# Schematic.net
KiCad netlist of a schematic drawn in Altium Designer
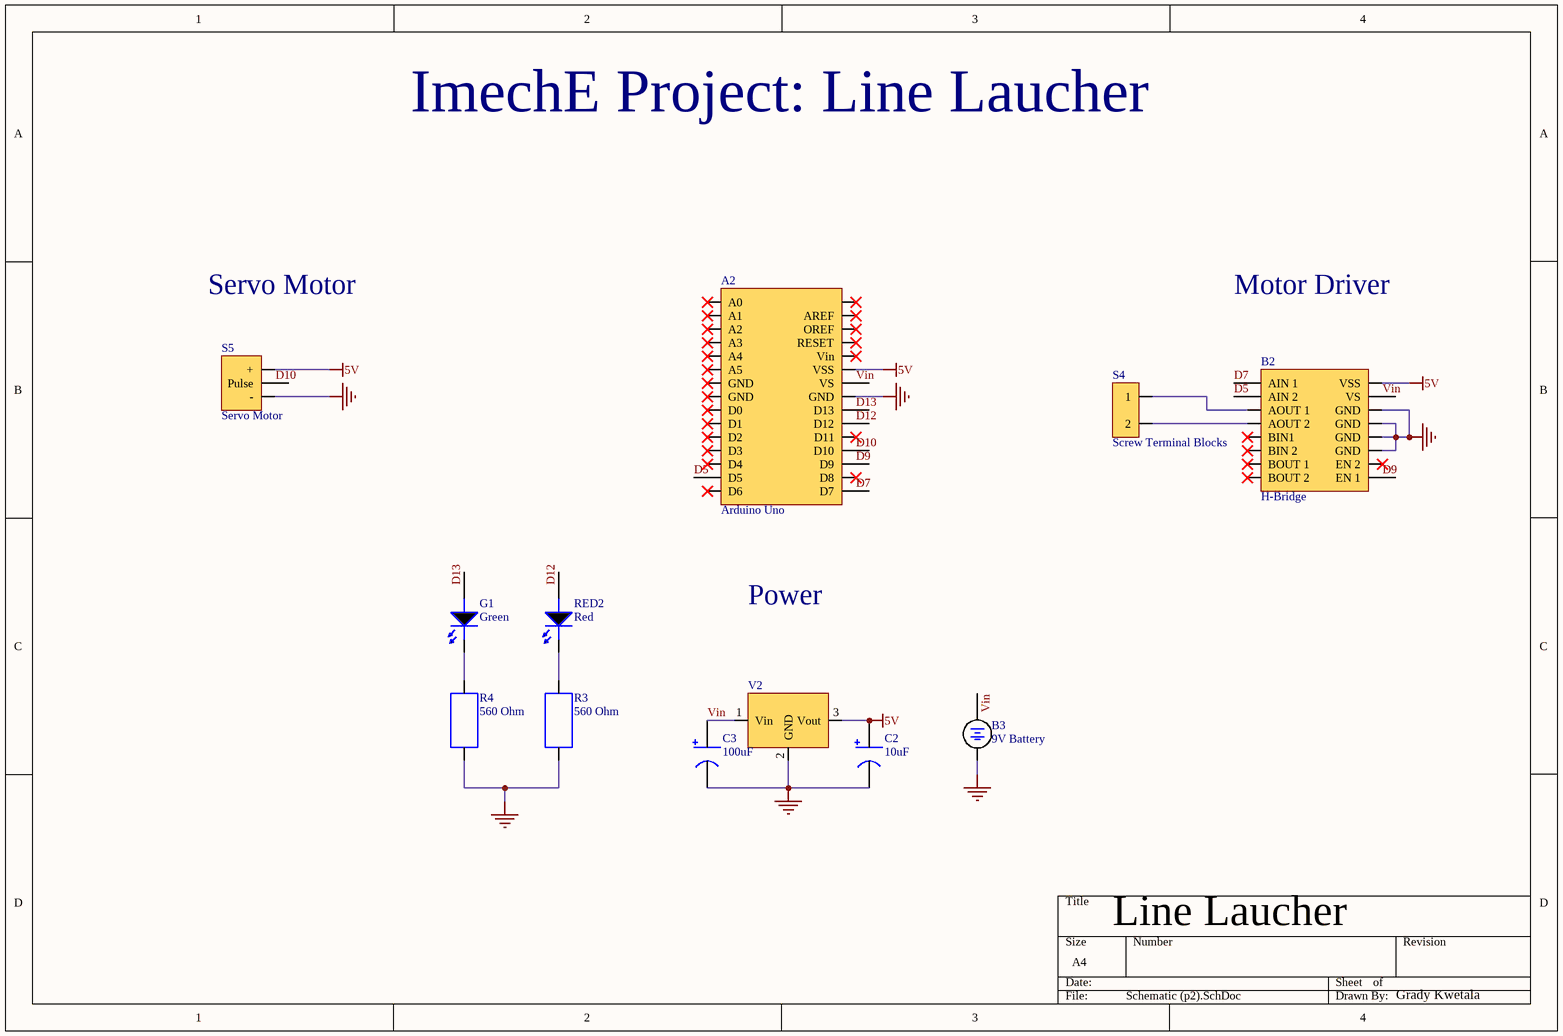
[diagram p0: Schematic (p2).SchDoc]

(export (version "E")
  (design (tool "Eeschema 10.0.6"))
  (components
    (comp (ref "A2")
      (value "Arduino Uno")
      (footprint "Arduino Uno")
      (description "16-bit Microcontrollers - MCU Mixed Signal MCU")
      (fields
        (field (name "MANUFACTURER") "Texas Instruments")
        (field (name "MANUFACTURER PART NUMBER") "MSP430FR5739IDA")
      )
      (libsource (lib "Schematic Library") (part "MSP430FR5739IDA"))
    )
    (comp (ref "B2")
      (value "H-Bridge")
      (footprint "H-Bridge")
      (description "TEXAS INSTRUMENTS - SN754410NE - IC, PERIPHERAL DRIVER, HALF-H, 1A, DIP16")
      (fields
        (field (name "MANUFACTURER") "Texas Instruments")
        (field (name "MANUFACTURER PART NUMBER") "SN754410NE")
      )
      (libsource (lib "Schematic Library") (part "SN754410NE"))
    )
    (comp (ref "B3")
      (value "9V Battery")
      (footprint "9V Battery")
      (description "BATTERY ALKALINE 9V")
      (fields
        (field (name "MANUFACTURER") "Panasonic")
        (field (name "MANUFACTURER PART NUMBER") "6LF22XWA/B")
      )
      (libsource (lib "Schematic Library") (part "6LF22XWA/B"))
    )
    (comp (ref "C2")
      (value "10uF")
      (footprint "10uF")
      (description "Cap Aluminum Lytic 10uF 400V 20% (10 X 16mm) Radial 5mm 150mA 8000h 105C Ammo Pack")
      (fields
        (field (name "MANUFACTURER") "Nichicon")
        (field (name "MANUFACTURER PART NUMBER") "UCY2G100MPD1TD")
      )
      (libsource (lib "Schematic Library") (part "UCY2G100MPD1TD"))
    )
    (comp (ref "C3") (value "100uF") (footprint "100uF") (libsource (lib "Schematic Library") (part "100uF")))
    (comp (ref "G1")
      (value "Green")
      (footprint "Green")
      (description "LED Uni-Color Green 574nm 2-Pin Chip LED T/R")
      (fields
        (field (name "MANUFACTURER") "Vishay Lite-On")
        (field (name "MANUFACTURER PART NUMBER") "LTST-C191KGKT")
      )
      (libsource (lib "Schematic Library") (part "LTST-C191KGKT"))
    )
    (comp (ref "R3")
      (value "560 Ohm")
      (footprint "560")
      (description "Res Thick Film 0805 560 Ohm 1% 0.125W(1/8W) ±100ppm/°C Molded SMD")
      (fields
        (field (name "MANUFACTURER") "TE Connectivity")
        (field (name "MANUFACTURER PART NUMBER") "1623252-1")
      )
      (libsource (lib "Schematic Library") (part "1623252-1"))
    )
    (comp (ref "R4")
      (value "560 Ohm")
      (footprint "560")
      (description "Res Thick Film 0805 560 Ohm 1% 0.125W(1/8W) ±100ppm/°C Molded SMD")
      (fields
        (field (name "MANUFACTURER") "TE Connectivity")
        (field (name "MANUFACTURER PART NUMBER") "1623252-1")
      )
      (libsource (lib "Schematic Library") (part "1623252-1"))
    )
    (comp (ref "RED2")
      (value "Red")
      (footprint "RED")
      (description "AVAGO TECHNOLOGIES   HSMC-C190.   LED, SMD, RED")
      (fields
        (field (name "MANUFACTURER") "Broadcom Avago")
        (field (name "MANUFACTURER PART NUMBER") "HSMC-C190")
      )
      (libsource (lib "Schematic Library") (part "HSMC-C190"))
    )
    (comp (ref "S4")
      (value "Screw Terminal Blocks")
      (footprint "Screw")
      (description "TERM BLOCK 2POS 45DEG 3.5MM PCB")
      (fields
        (field (name "MANUFACTURER") "Phoenix Contact")
        (field (name "MANUFACTURER PART NUMBER") "1988956")
      )
      (libsource (lib "Schematic Library") (part "1988956"))
    )
    (comp (ref "S5")
      (value "Servo Motor")
      (footprint "Servo Motor")
      (description "GEARMOTOR 6VDC SERVO")
      (fields (field (name "MANUFACTURER") "Parallax") (field (name "MANUFACTURER PART NUMBER") "900-00008"))
      (libsource (lib "Schematic Library") (part "900-00008"))
    )
    (comp (ref "V2")
      (value "Voltage Regular")
      (footprint "Voltage regulator")
      (description "STMICROELECTRONICS   L78M05CDT-TR   LINEAR VOLTAGE REGULATOR, 5V, DPAK-3")
      (fields
        (field (name "MANUFACTURER") "STMicroelectronics")
        (field (name "MANUFACTURER PART NUMBER") "L78M05CDT-TR")
      )
      (libsource (lib "Schematic Library") (part "L78M05CDT-TR"))
    )
  )
  (nets
    (net (code "1") (name "/D5") (class "Default")
      (node (ref "A2") (pin "14") (pinfunction "D5_14") (pintype "passive"))
      (node (ref "B2") (pin "2") (pinfunction "AIN_2_2") (pintype "passive"))
    )
    (net (code "2") (name "/D7") (class "Default")
      (node (ref "A2") (pin "16") (pinfunction "D7_16") (pintype "passive"))
      (node (ref "B2") (pin "1") (pinfunction "AIN_1_1") (pintype "passive"))
    )
    (net (code "3") (name "/D9") (class "Default")
      (node (ref "A2") (pin "18") (pinfunction "D9_18") (pintype "passive"))
      (node (ref "B2") (pin "9") (pinfunction "EN_1_9") (pintype "passive"))
    )
    (net (code "4") (name "/D10") (class "Default")
      (node (ref "A2") (pin "19") (pinfunction "D10_19") (pintype "passive"))
      (node (ref "S5") (pin "2") (pinfunction "Pulse_2") (pintype "passive"))
    )
    (net (code "5") (name "/D12") (class "Default")
      (node (ref "A2") (pin "21") (pinfunction "D12_21") (pintype "passive"))
      (node (ref "RED2") (pin "2") (pinfunction "+_2") (pintype "passive"))
    )
    (net (code "6") (name "/D13") (class "Default")
      (node (ref "A2") (pin "22") (pinfunction "D13_22") (pintype "passive"))
      (node (ref "G1") (pin "2") (pinfunction "+_2") (pintype "passive"))
    )
    (net (code "7") (name "/Vin") (class "Default")
      (node (ref "A2") (pin "24") (pinfunction "VS_24") (pintype "passive"))
      (node (ref "B2") (pin "15") (pinfunction "VS_15") (pintype "passive"))
      (node (ref "B3") (pin "1") (pinfunction "+_1") (pintype "passive"))
      (node (ref "C3") (pin "2") (pinfunction "2_2") (pintype "passive"))
      (node (ref "V2") (pin "1") (pinfunction "Vin_1") (pintype "passive"))
    )
    (net (code "8") (name "5V") (class "Default")
      (node (ref "A2") (pin "25") (pinfunction "VSS_25") (pintype "passive"))
      (node (ref "B2") (pin "16") (pinfunction "VSS_16") (pintype "passive"))
      (node (ref "C2") (pin "2") (pinfunction "2_2") (pintype "passive"))
      (node (ref "S5") (pin "1") (pinfunction "+_1") (pintype "passive"))
      (node (ref "V2") (pin "3") (pinfunction "Vout_3") (pintype "passive"))
    )
    (net (code "9") (name "GND") (class "Default")
      (node (ref "A2") (pin "23") (pinfunction "GND_23") (pintype "passive"))
      (node (ref "B2") (pin "11") (pinfunction "GND_11") (pintype "passive"))
      (node (ref "B2") (pin "12") (pinfunction "GND_12") (pintype "passive"))
      (node (ref "B2") (pin "13") (pinfunction "GND_13") (pintype "passive"))
      (node (ref "B2") (pin "14") (pinfunction "GND_14") (pintype "passive"))
      (node (ref "B3") (pin "2") (pinfunction "-_2") (pintype "passive"))
      (node (ref "C2") (pin "1") (pinfunction "1_1") (pintype "passive"))
      (node (ref "C3") (pin "1") (pinfunction "1_1") (pintype "passive"))
      (node (ref "R3") (pin "1") (pinfunction "1_1") (pintype "passive"))
      (node (ref "R4") (pin "1") (pinfunction "1_1") (pintype "passive"))
      (node (ref "S5") (pin "3") (pinfunction "-_3") (pintype "passive"))
      (node (ref "V2") (pin "2") (pinfunction "GND_2") (pintype "passive"))
    )
    (net (code "10") (name "Net-(B2-AOUT_1)") (class "Default")
      (node (ref "B2") (pin "3") (pinfunction "AOUT_1_3") (pintype "passive"))
      (node (ref "S4") (pin "1") (pinfunction "1_1") (pintype "passive"))
    )
    (net (code "11") (name "Net-(B2-AOUT_2)") (class "Default")
      (node (ref "B2") (pin "4") (pinfunction "AOUT_2_4") (pintype "passive"))
      (node (ref "S4") (pin "2") (pinfunction "2_2") (pintype "passive"))
    )
    (net (code "12") (name "Net-(G1--)") (class "Default")
      (node (ref "G1") (pin "1") (pinfunction "-_1") (pintype "passive"))
      (node (ref "R4") (pin "2") (pinfunction "2_2") (pintype "passive"))
    )
    (net (code "13") (name "Net-(RED2--)") (class "Default")
      (node (ref "R3") (pin "2") (pinfunction "2_2") (pintype "passive"))
      (node (ref "RED2") (pin "1") (pinfunction "-_1") (pintype "passive"))
    )
    (net (code "14") (name "unconnected-(A2-A0-Pad1)") (class "Default")
      (node (ref "A2") (pin "1") (pinfunction "A0_1") (pintype "passive+no_connect"))
    )
    (net (code "15") (name "unconnected-(A2-A1-Pad2)") (class "Default")
      (node (ref "A2") (pin "2") (pinfunction "A1_2") (pintype "passive+no_connect"))
    )
    (net (code "16") (name "unconnected-(A2-A2-Pad3)") (class "Default")
      (node (ref "A2") (pin "3") (pinfunction "A2_3") (pintype "passive+no_connect"))
    )
    (net (code "17") (name "unconnected-(A2-A3-Pad4)") (class "Default")
      (node (ref "A2") (pin "4") (pinfunction "A3_4") (pintype "passive+no_connect"))
    )
    (net (code "18") (name "unconnected-(A2-A4-Pad5)") (class "Default")
      (node (ref "A2") (pin "5") (pinfunction "A4_5") (pintype "passive+no_connect"))
    )
    (net (code "19") (name "unconnected-(A2-A5-Pad6)") (class "Default")
      (node (ref "A2") (pin "6") (pinfunction "A5_6") (pintype "passive+no_connect"))
    )
    (net (code "20") (name "unconnected-(A2-AREF-Pad29)") (class "Default")
      (node (ref "A2") (pin "29") (pinfunction "AREF_29") (pintype "passive+no_connect"))
    )
    (net (code "21") (name "unconnected-(A2-D0-Pad9)") (class "Default")
      (node (ref "A2") (pin "9") (pinfunction "D0_9") (pintype "passive+no_connect"))
    )
    (net (code "22") (name "unconnected-(A2-D1-Pad10)") (class "Default")
      (node (ref "A2") (pin "10") (pinfunction "D1_10") (pintype "passive+no_connect"))
    )
    (net (code "23") (name "unconnected-(A2-D2-Pad11)") (class "Default")
      (node (ref "A2") (pin "11") (pinfunction "D2_11") (pintype "passive+no_connect"))
    )
    (net (code "24") (name "unconnected-(A2-D3-Pad12)") (class "Default")
      (node (ref "A2") (pin "12") (pinfunction "D3_12") (pintype "passive+no_connect"))
    )
    (net (code "25") (name "unconnected-(A2-D4-Pad13)") (class "Default")
      (node (ref "A2") (pin "13") (pinfunction "D4_13") (pintype "passive+no_connect"))
    )
    (net (code "26") (name "unconnected-(A2-D6-Pad15)") (class "Default")
      (node (ref "A2") (pin "15") (pinfunction "D6_15") (pintype "passive+no_connect"))
    )
    (net (code "27") (name "unconnected-(A2-D8-Pad17)") (class "Default")
      (node (ref "A2") (pin "17") (pinfunction "D8_17") (pintype "passive+no_connect"))
    )
    (net (code "28") (name "unconnected-(A2-D11-Pad20)") (class "Default")
      (node (ref "A2") (pin "20") (pinfunction "D11_20") (pintype "passive+no_connect"))
    )
    (net (code "29") (name "unconnected-(A2-GND-Pad7)") (class "Default")
      (node (ref "A2") (pin "7") (pinfunction "GND_7") (pintype "passive+no_connect"))
    )
    (net (code "30") (name "unconnected-(A2-GND-Pad8)") (class "Default")
      (node (ref "A2") (pin "8") (pinfunction "GND_8") (pintype "passive+no_connect"))
    )
    (net (code "31") (name "unconnected-(A2-OREF-Pad28)") (class "Default")
      (node (ref "A2") (pin "28") (pinfunction "OREF_28") (pintype "passive+no_connect"))
    )
    (net (code "32") (name "unconnected-(A2-Pad30)") (class "Default")
      (node (ref "A2") (pin "30") (pinfunction "30_30") (pintype "passive+no_connect"))
    )
    (net (code "33") (name "unconnected-(A2-RESET-Pad27)") (class "Default")
      (node (ref "A2") (pin "27") (pinfunction "RESET_27") (pintype "passive+no_connect"))
    )
    (net (code "34") (name "unconnected-(A2-Vin-Pad26)") (class "Default")
      (node (ref "A2") (pin "26") (pinfunction "Vin_26") (pintype "passive+no_connect"))
    )
    (net (code "35") (name "unconnected-(B2-BIN1-Pad5)") (class "Default")
      (node (ref "B2") (pin "5") (pinfunction "BIN1_5") (pintype "passive+no_connect"))
    )
    (net (code "36") (name "unconnected-(B2-BIN_2-Pad6)") (class "Default")
      (node (ref "B2") (pin "6") (pinfunction "BIN_2_6") (pintype "passive+no_connect"))
    )
    (net (code "37") (name "unconnected-(B2-BOUT_1-Pad7)") (class "Default")
      (node (ref "B2") (pin "7") (pinfunction "BOUT_1_7") (pintype "passive+no_connect"))
    )
    (net (code "38") (name "unconnected-(B2-BOUT_2-Pad8)") (class "Default")
      (node (ref "B2") (pin "8") (pinfunction "BOUT_2_8") (pintype "passive+no_connect"))
    )
    (net (code "39") (name "unconnected-(B2-EN_2-Pad10)") (class "Default")
      (node (ref "B2") (pin "10") (pinfunction "EN_2_10") (pintype "passive+no_connect"))
    )
  )
)
